# knxhome.net
KiCad netlist of a schematic drawn in EAGLE
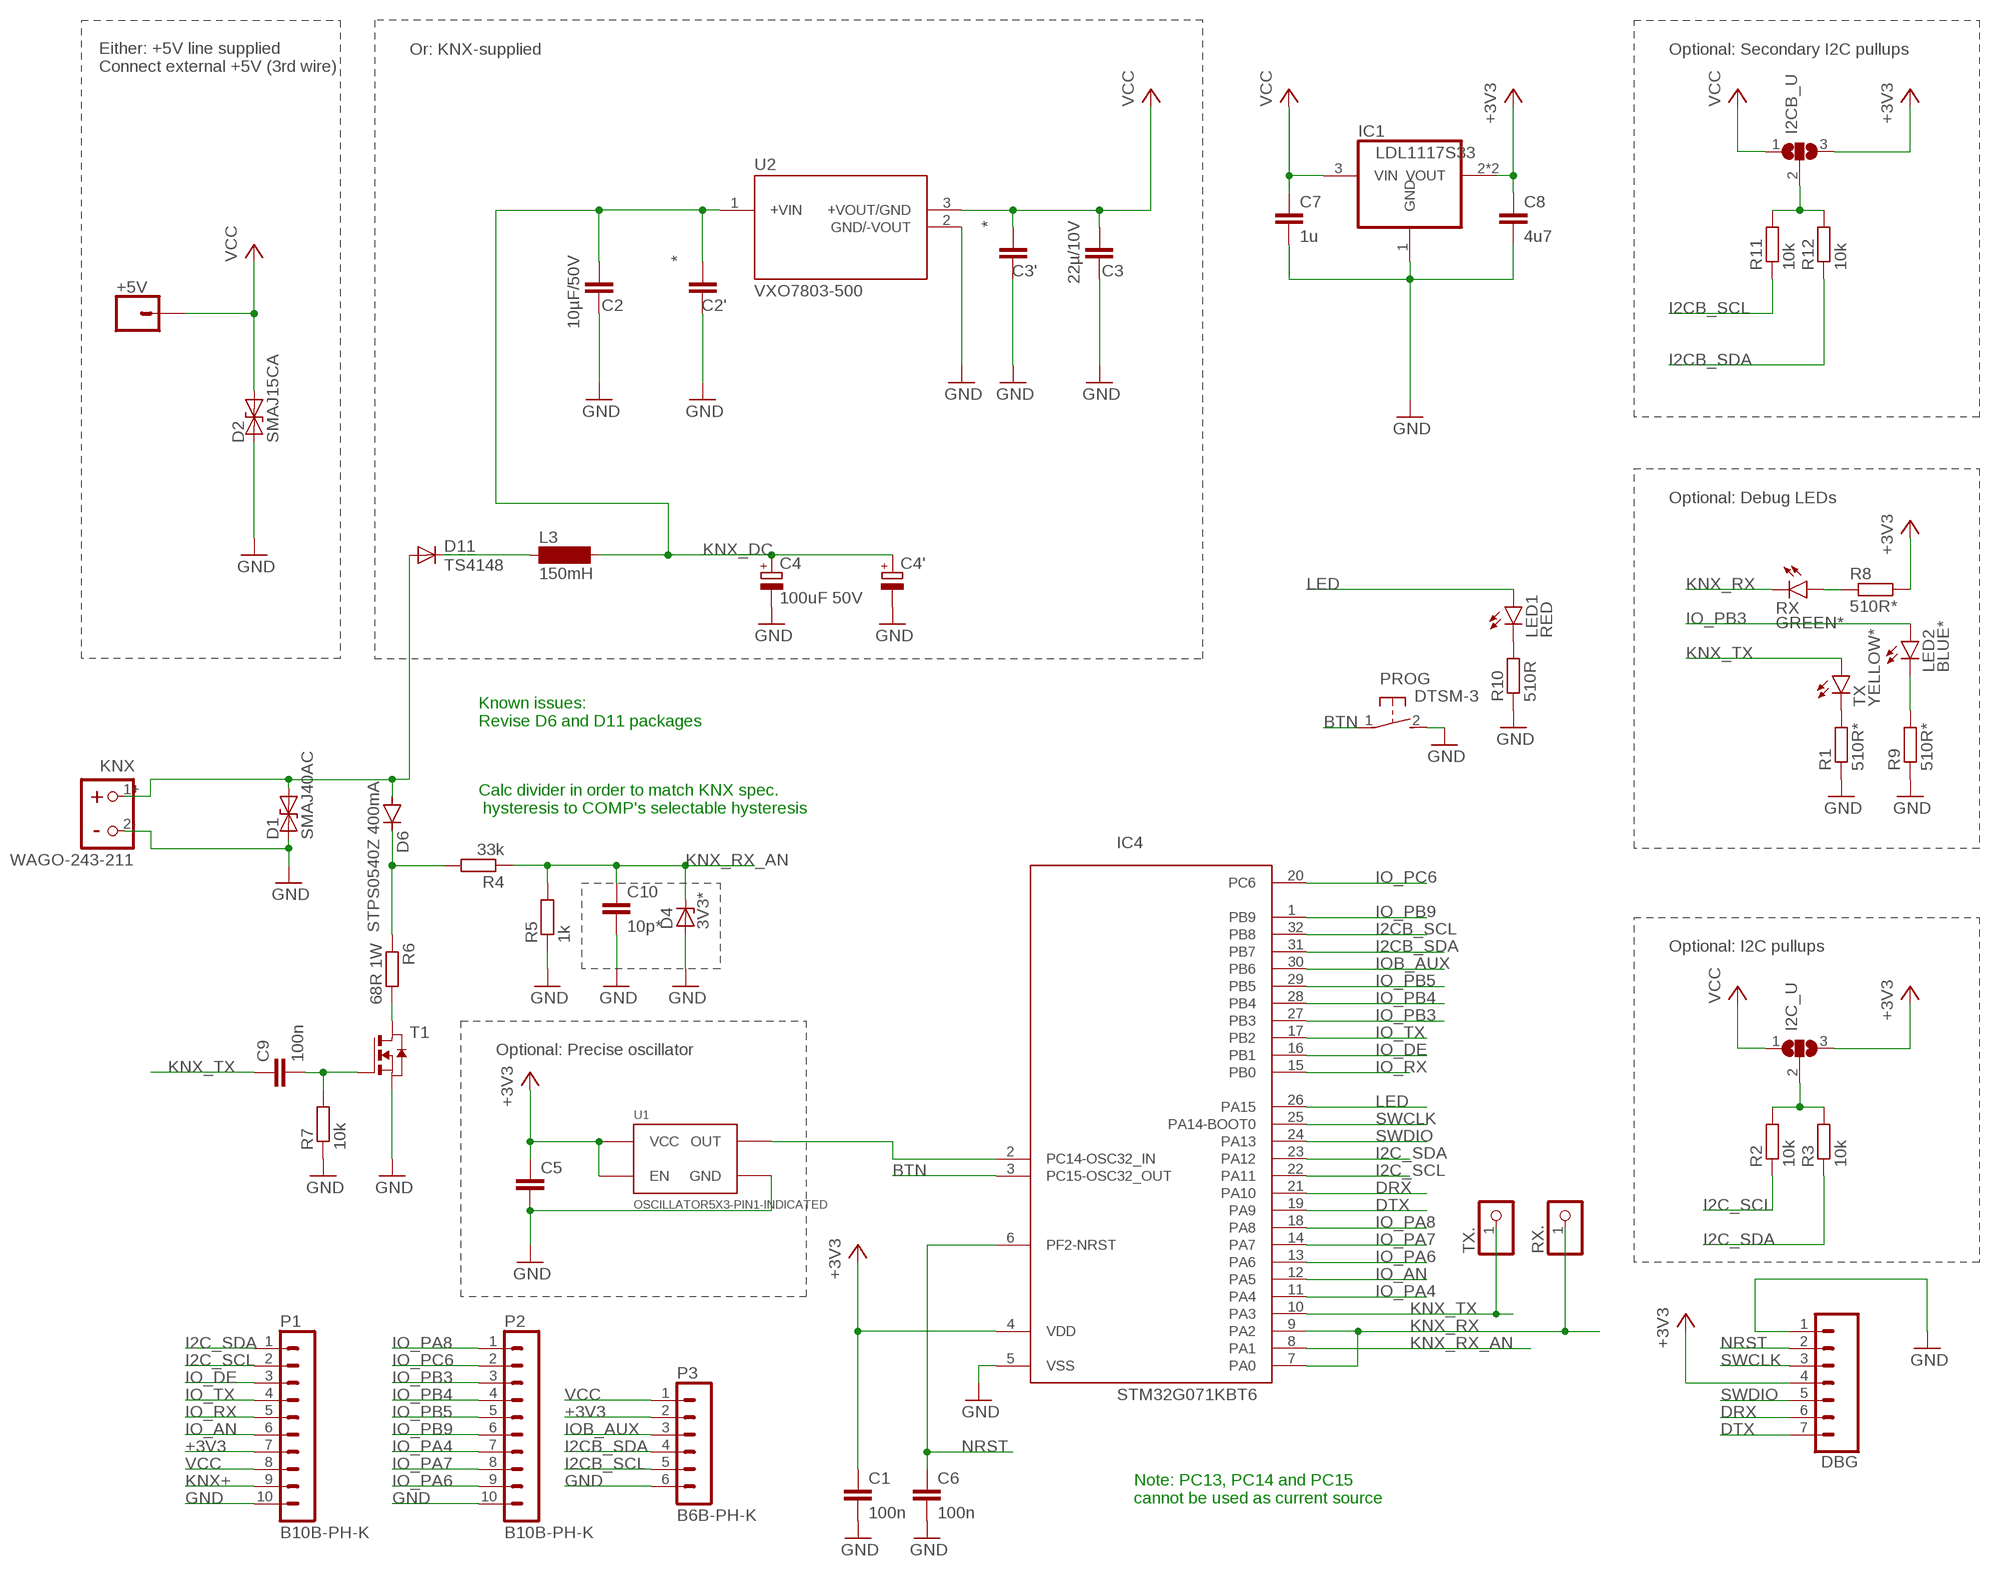
[diagram p0: schematic, sheet 1]

(export (version "E")
  (design (tool "Eeschema 10.0.6"))
  (components
    (comp (ref "+5V")
      (value "CONN_01PTH_LONGPAD")
      (footprint "eagle-import:1X01_LONGPAD")
      (libsource (lib "eagle-import") (part "CONN_01PTH_LONGPAD"))
    )
    (comp (ref "C1")
      (value "100n")
      (footprint "eagle-import:C0805")
      (libsource (lib "eagle-import") (part "C-EUC0805"))
    )
    (comp (ref "C2")
      (value "10µF/50V")
      (footprint "eagle-import:C1210")
      (libsource (lib "eagle-import") (part "C-EUC1210"))
    )
    (comp (ref "C2'")
      (value "*")
      (footprint "eagle-import:C1210")
      (libsource (lib "eagle-import") (part "C-EUC1210"))
    )
    (comp (ref "C3")
      (value "22µ/10V")
      (footprint "eagle-import:C1210")
      (libsource (lib "eagle-import") (part "C-EUC1210"))
    )
    (comp (ref "C3'")
      (value "*")
      (footprint "eagle-import:C1210")
      (libsource (lib "eagle-import") (part "C-EUC1210"))
    )
    (comp (ref "C4")
      (value "100uF 50V")
      (footprint "eagle-import:E3,5-8")
      (libsource (lib "eagle-import") (part "CPOL-EUE3.5-8"))
    )
    (comp (ref "C4'")
      (value "CPOL-EU153CLV-0810")
      (footprint "eagle-import:153CLV-0810")
      (libsource (lib "eagle-import") (part "resistor_348_CPOL-EU153CLV-0810"))
    )
    (comp (ref "C5")
      (value "C-EUC0805")
      (footprint "eagle-import:C0805")
      (libsource (lib "eagle-import") (part "C-EUC0805"))
    )
    (comp (ref "C6")
      (value "100n")
      (footprint "eagle-import:C0805")
      (libsource (lib "eagle-import") (part "C-EUC0805"))
    )
    (comp (ref "C7")
      (value "1u")
      (footprint "eagle-import:C0805")
      (libsource (lib "eagle-import") (part "C-EUC0805"))
    )
    (comp (ref "C8")
      (value "4u7")
      (footprint "eagle-import:C0805")
      (libsource (lib "eagle-import") (part "C-EUC0805"))
    )
    (comp (ref "C9")
      (value "100n")
      (footprint "eagle-import:C0805")
      (libsource (lib "eagle-import") (part "C-EUC0805"))
    )
    (comp (ref "C10")
      (value "10p*")
      (footprint "eagle-import:C0805")
      (libsource (lib "eagle-import") (part "C-EUC0805"))
    )
    (comp (ref "D1")
      (value "SMAJ40AC")
      (footprint "eagle-import:DO-214AC")
      (libsource (lib "eagle-import") (part "SMAJ40AC"))
    )
    (comp (ref "D2")
      (value "SMAJ15CA")
      (footprint "eagle-import:DO-214AC")
      (libsource (lib "eagle-import") (part "SMAJ40AC"))
    )
    (comp (ref "D4")
      (value "3V3*")
      (footprint "eagle-import:SOT23")
      (libsource (lib "eagle-import") (part "ZENER-DIODESOT23"))
    )
    (comp (ref "D6")
      (value "STPS0540Z 400mA")
      (footprint "eagle-import:SOD123")
      (libsource (lib "eagle-import") (part "diode_210_DIODE-SOD123"))
    )
    (comp (ref "D11")
      (value "TS4148")
      (footprint "eagle-import:SOD123")
      (libsource (lib "eagle-import") (part "DIODE-SOD123"))
    )
    (comp (ref "DBG")
      (value "CONN_07LOCK")
      (footprint "eagle-import:1X07_LOCK")
      (libsource (lib "eagle-import") (part "CONN_07LOCK"))
    )
    (comp (ref "I2CB_U")
      (value "SJ2W")
      (footprint "eagle-import:SJ_2")
      (libsource (lib "eagle-import") (part "SJ2W"))
    )
    (comp (ref "I2C_U")
      (value "SJ2W")
      (footprint "eagle-import:SJ_2")
      (libsource (lib "eagle-import") (part "SJ2W"))
    )
    (comp (ref "IC1")
      (value "LDL1117S33")
      (footprint "eagle-import:SOT223")
      (fields (field (name "MPN") "REG1117"))
      (libsource (lib "eagle-import") (part "REG1117"))
    )
    (comp (ref "IC4")
      (value "STM32G071KBT6")
      (footprint "eagle-import:LQFP32")
      (libsource (lib "eagle-import") (part "STM32G071KBT6"))
    )
    (comp (ref "KNX")
      (value "WAGO-243-211")
      (footprint "eagle-import:WAGO-243-211")
      (libsource (lib "eagle-import") (part "WAGO-243-211"))
    )
    (comp (ref "L3")
      (value "150mH")
      (footprint "eagle-import:BS11_LIEGEND")
      (libsource (lib "eagle-import") (part "SD12BS11_LIEGEND"))
    )
    (comp (ref "LED1")
      (value "RED")
      (footprint "eagle-import:CHIPLED_1206")
      (libsource (lib "eagle-import") (part "LEDCHIPLED_1206"))
    )
    (comp (ref "LED2")
      (value "BLUE*")
      (footprint "eagle-import:CHIPLED_1206")
      (libsource (lib "eagle-import") (part "LEDCHIPLED_1206"))
    )
    (comp (ref "P1")
      (value "B10B-PH-K")
      (footprint "eagle-import:B10B-PH-K")
      (libsource (lib "eagle-import") (part "B10B-PH-K"))
    )
    (comp (ref "P2")
      (value "B10B-PH-K")
      (footprint "eagle-import:B10B-PH-K")
      (libsource (lib "eagle-import") (part "B10B-PH-K"))
    )
    (comp (ref "P3")
      (value "B6B-PH-K")
      (footprint "eagle-import:B6B-PH-K")
      (libsource (lib "eagle-import") (part "B6B-PH-K"))
    )
    (comp (ref "PROG")
      (value "DTSM-3")
      (footprint "eagle-import:DTSM-3")
      (libsource (lib "eagle-import") (part "DTSM-3"))
    )
    (comp (ref "R1")
      (value "510R*")
      (footprint "eagle-import:R0805")
      (libsource (lib "eagle-import") (part "R-EU_R0805"))
    )
    (comp (ref "R2")
      (value "10k")
      (footprint "eagle-import:R0805")
      (libsource (lib "eagle-import") (part "R-EU_R0805"))
    )
    (comp (ref "R3")
      (value "10k")
      (footprint "eagle-import:R0805")
      (libsource (lib "eagle-import") (part "R-EU_R0805"))
    )
    (comp (ref "R4")
      (value "33k")
      (footprint "eagle-import:R0805")
      (libsource (lib "eagle-import") (part "R-EU_R0805"))
    )
    (comp (ref "R5")
      (value "1k")
      (footprint "eagle-import:R0805")
      (libsource (lib "eagle-import") (part "R-EU_R0805"))
    )
    (comp (ref "R6")
      (value "68R 1W")
      (footprint "eagle-import:R2512")
      (libsource (lib "eagle-import") (part "R-EU_R2512"))
    )
    (comp (ref "R7")
      (value "10k")
      (footprint "eagle-import:R0805")
      (libsource (lib "eagle-import") (part "R-EU_R0805"))
    )
    (comp (ref "R8")
      (value "510R*")
      (footprint "eagle-import:R0805")
      (libsource (lib "eagle-import") (part "R-EU_R0805"))
    )
    (comp (ref "R9")
      (value "510R*")
      (footprint "eagle-import:R0805")
      (libsource (lib "eagle-import") (part "R-EU_R0805"))
    )
    (comp (ref "R10")
      (value "510R")
      (footprint "eagle-import:R0805")
      (libsource (lib "eagle-import") (part "R-EU_R0805"))
    )
    (comp (ref "R11")
      (value "10k")
      (footprint "eagle-import:R0805")
      (libsource (lib "eagle-import") (part "R-EU_R0805"))
    )
    (comp (ref "R12")
      (value "10k")
      (footprint "eagle-import:R0805")
      (libsource (lib "eagle-import") (part "R-EU_R0805"))
    )
    (comp (ref "RX")
      (value "GREEN*")
      (footprint "eagle-import:CHIPLED_1206")
      (libsource (lib "eagle-import") (part "LEDCHIPLED_1206"))
    )
    (comp (ref "RX.")
      (value "PINHD-1X1")
      (footprint "eagle-import:1X01")
      (libsource (lib "eagle-import") (part "PINHD-1X1"))
    )
    (comp (ref "T1")
      (value "NMOSSOT23")
      (footprint "eagle-import:SOT-23")
      (libsource (lib "eagle-import") (part "NMOSSOT23"))
    )
    (comp (ref "TX")
      (value "YELLOW*")
      (footprint "eagle-import:CHIPLED_1206")
      (libsource (lib "eagle-import") (part "LEDCHIPLED_1206"))
    )
    (comp (ref "TX.")
      (value "PINHD-1X1")
      (footprint "eagle-import:1X01")
      (libsource (lib "eagle-import") (part "PINHD-1X1"))
    )
    (comp (ref "U1")
      (value "OSCILLATOR5X3-PIN1-INDICATED")
      (footprint "eagle-import:CRYSTAL-OSC-SMD-5X3")
      (libsource (lib "eagle-import") (part "OSCILLATOR5X3-PIN1-INDICATED"))
    )
    (comp (ref "U2")
      (value "VXO7803-500")
      (footprint "eagle-import:CONV_VXO7803-500")
      (fields (field (name "MANUFACTURER") "CUI Inc"))
      (libsource (lib "eagle-import") (part "VXO7803-500"))
    )
  )
  (nets
    (net (code "1") (name "+3V3") (class "Default")
      (node (ref "C1") (pin "1") (pinfunction "1_1") (pintype "passive"))
      (node (ref "C5") (pin "1") (pinfunction "1_1") (pintype "passive"))
      (node (ref "C8") (pin "1") (pinfunction "1_1") (pintype "passive"))
      (node (ref "DBG") (pin "4") (pinfunction "4_4") (pintype "passive"))
      (node (ref "I2CB_U") (pin "3") (pinfunction "3_3") (pintype "passive"))
      (node (ref "I2C_U") (pin "3") (pinfunction "3_3") (pintype "passive"))
      (node (ref "IC1") (pin "2") (pinfunction "VOUT_2") (pintype "output"))
      (node (ref "IC1") (pin "4") (pinfunction "VOUT_4") (pintype "output"))
      (node (ref "IC4") (pin "4") (pinfunction "VDD_4") (pintype "power_in"))
      (node (ref "P1") (pin "7") (pinfunction "7_7") (pintype "passive"))
      (node (ref "P3") (pin "2") (pinfunction "2_2") (pintype "passive"))
      (node (ref "R8") (pin "2") (pinfunction "2_2") (pintype "passive"))
      (node (ref "U1") (pin "1") (pinfunction "EN_1") (pintype "bidirectional"))
      (node (ref "U1") (pin "4") (pinfunction "VCC_4") (pintype "bidirectional"))
    )
    (net (code "2") (name "/BTN") (class "Default")
      (node (ref "IC4") (pin "3") (pinfunction "PC15-OSC32_OUT_3") (pintype "bidirectional"))
      (node (ref "PROG") (pin "1") (pinfunction "1_1") (pintype "passive"))
    )
    (net (code "3") (name "/DRX") (class "Default")
      (node (ref "DBG") (pin "6") (pinfunction "6_6") (pintype "passive"))
      (node (ref "IC4") (pin "21") (pinfunction "PA10_21") (pintype "bidirectional"))
    )
    (net (code "4") (name "/DTX") (class "Default")
      (node (ref "DBG") (pin "7") (pinfunction "7_7") (pintype "passive"))
      (node (ref "IC4") (pin "19") (pinfunction "PA9_19") (pintype "bidirectional"))
    )
    (net (code "5") (name "/I2CB_SCL") (class "Default")
      (node (ref "IC4") (pin "32") (pinfunction "PB8_32") (pintype "bidirectional"))
      (node (ref "P3") (pin "5") (pinfunction "5_5") (pintype "passive"))
      (node (ref "R11") (pin "1") (pinfunction "1_1") (pintype "passive"))
    )
    (net (code "6") (name "/I2CB_SDA") (class "Default")
      (node (ref "IC4") (pin "31") (pinfunction "PB7_31") (pintype "bidirectional"))
      (node (ref "P3") (pin "4") (pinfunction "4_4") (pintype "passive"))
      (node (ref "R12") (pin "1") (pinfunction "1_1") (pintype "passive"))
    )
    (net (code "7") (name "/I2C_SCL") (class "Default")
      (node (ref "IC4") (pin "22") (pinfunction "PA11_22") (pintype "bidirectional"))
      (node (ref "P1") (pin "2") (pinfunction "2_2") (pintype "passive"))
      (node (ref "R2") (pin "1") (pinfunction "1_1") (pintype "passive"))
    )
    (net (code "8") (name "/I2C_SDA") (class "Default")
      (node (ref "IC4") (pin "23") (pinfunction "PA12_23") (pintype "bidirectional"))
      (node (ref "P1") (pin "1") (pinfunction "1_1") (pintype "passive"))
      (node (ref "R3") (pin "1") (pinfunction "1_1") (pintype "passive"))
    )
    (net (code "9") (name "/IOB_AUX") (class "Default")
      (node (ref "IC4") (pin "30") (pinfunction "PB6_30") (pintype "bidirectional"))
      (node (ref "P3") (pin "3") (pinfunction "3_3") (pintype "passive"))
    )
    (net (code "10") (name "/IO_AN") (class "Default")
      (node (ref "IC4") (pin "12") (pinfunction "PA5_12") (pintype "bidirectional"))
      (node (ref "P1") (pin "6") (pinfunction "6_6") (pintype "passive"))
    )
    (net (code "11") (name "/IO_DE") (class "Default")
      (node (ref "IC4") (pin "16") (pinfunction "PB1_16") (pintype "bidirectional"))
      (node (ref "P1") (pin "3") (pinfunction "3_3") (pintype "passive"))
    )
    (net (code "12") (name "/IO_PA4") (class "Default")
      (node (ref "IC4") (pin "11") (pinfunction "PA4_11") (pintype "bidirectional"))
      (node (ref "P2") (pin "7") (pinfunction "7_7") (pintype "passive"))
    )
    (net (code "13") (name "/IO_PA6") (class "Default")
      (node (ref "IC4") (pin "13") (pinfunction "PA6_13") (pintype "bidirectional"))
      (node (ref "P2") (pin "9") (pinfunction "9_9") (pintype "passive"))
    )
    (net (code "14") (name "/IO_PA7") (class "Default")
      (node (ref "IC4") (pin "14") (pinfunction "PA7_14") (pintype "bidirectional"))
      (node (ref "P2") (pin "8") (pinfunction "8_8") (pintype "passive"))
    )
    (net (code "15") (name "/IO_PA8") (class "Default")
      (node (ref "IC4") (pin "18") (pinfunction "PA8_18") (pintype "bidirectional"))
      (node (ref "P2") (pin "1") (pinfunction "1_1") (pintype "passive"))
    )
    (net (code "16") (name "/IO_PB3") (class "Default")
      (node (ref "IC4") (pin "27") (pinfunction "PB3_27") (pintype "bidirectional"))
      (node (ref "LED2") (pin "A") (pinfunction "A_A") (pintype "passive"))
      (node (ref "P2") (pin "3") (pinfunction "3_3") (pintype "passive"))
    )
    (net (code "17") (name "/IO_PB4") (class "Default")
      (node (ref "IC4") (pin "28") (pinfunction "PB4_28") (pintype "bidirectional"))
      (node (ref "P2") (pin "4") (pinfunction "4_4") (pintype "passive"))
    )
    (net (code "18") (name "/IO_PB5") (class "Default")
      (node (ref "IC4") (pin "29") (pinfunction "PB5_29") (pintype "bidirectional"))
      (node (ref "P2") (pin "5") (pinfunction "5_5") (pintype "passive"))
    )
    (net (code "19") (name "/IO_PB9") (class "Default")
      (node (ref "IC4") (pin "1") (pinfunction "PB9_1") (pintype "bidirectional"))
      (node (ref "P2") (pin "6") (pinfunction "6_6") (pintype "passive"))
    )
    (net (code "20") (name "/IO_PC6") (class "Default")
      (node (ref "IC4") (pin "20") (pinfunction "PC6_20") (pintype "bidirectional"))
      (node (ref "P2") (pin "2") (pinfunction "2_2") (pintype "passive"))
    )
    (net (code "21") (name "/IO_RX") (class "Default")
      (node (ref "IC4") (pin "15") (pinfunction "PB0_15") (pintype "bidirectional"))
      (node (ref "P1") (pin "5") (pinfunction "5_5") (pintype "passive"))
    )
    (net (code "22") (name "/IO_TX") (class "Default")
      (node (ref "IC4") (pin "17") (pinfunction "PB2_17") (pintype "bidirectional"))
      (node (ref "P1") (pin "4") (pinfunction "4_4") (pintype "passive"))
    )
    (net (code "23") (name "/KNX+") (class "Default")
      (node (ref "D1") (pin "C") (pinfunction "C_C") (pintype "passive"))
      (node (ref "D11") (pin "A") (pinfunction "A_A") (pintype "passive"))
      (node (ref "D6") (pin "A") (pinfunction "A_A") (pintype "passive"))
      (node (ref "KNX") (pin "1+") (pinfunction "1+_1+") (pintype "passive"))
      (node (ref "P1") (pin "9") (pinfunction "9_9") (pintype "passive"))
    )
    (net (code "24") (name "/KNX_DC") (class "Default")
      (node (ref "C2") (pin "2") (pinfunction "2_2") (pintype "passive"))
      (node (ref "C2'") (pin "2") (pinfunction "2_2") (pintype "passive"))
      (node (ref "C4") (pin "+") (pinfunction "+_+") (pintype "passive"))
      (node (ref "C4'") (pin "+") (pinfunction "+_+") (pintype "passive"))
      (node (ref "L3") (pin "2") (pinfunction "2_2") (pintype "passive"))
      (node (ref "U2") (pin "1") (pinfunction "+VIN_1") (pintype "input"))
    )
    (net (code "25") (name "/KNX_RX") (class "Default")
      (node (ref "IC4") (pin "7") (pinfunction "PA0_7") (pintype "bidirectional"))
      (node (ref "IC4") (pin "9") (pinfunction "PA2_9") (pintype "bidirectional"))
      (node (ref "RX") (pin "C") (pinfunction "C_C") (pintype "passive"))
      (node (ref "RX.") (pin "1") (pinfunction "1_1") (pintype "passive"))
    )
    (net (code "26") (name "/KNX_RX_AN") (class "Default")
      (node (ref "C10") (pin "1") (pinfunction "1_1") (pintype "passive"))
      (node (ref "D4") (pin "3") (pinfunction "C_3") (pintype "passive"))
      (node (ref "IC4") (pin "8") (pinfunction "PA1_8") (pintype "bidirectional"))
      (node (ref "R4") (pin "1") (pinfunction "1_1") (pintype "passive"))
      (node (ref "R5") (pin "2") (pinfunction "2_2") (pintype "passive"))
    )
    (net (code "27") (name "/KNX_TX") (class "Default")
      (node (ref "C9") (pin "1") (pinfunction "1_1") (pintype "passive"))
      (node (ref "IC4") (pin "10") (pinfunction "PA3_10") (pintype "bidirectional"))
      (node (ref "TX") (pin "A") (pinfunction "A_A") (pintype "passive"))
      (node (ref "TX.") (pin "1") (pinfunction "1_1") (pintype "passive"))
    )
    (net (code "28") (name "/LED") (class "Default")
      (node (ref "IC4") (pin "26") (pinfunction "PA15_26") (pintype "bidirectional"))
      (node (ref "LED1") (pin "A") (pinfunction "A_A") (pintype "passive"))
    )
    (net (code "29") (name "/NRST") (class "Default")
      (node (ref "C6") (pin "1") (pinfunction "1_1") (pintype "passive"))
      (node (ref "DBG") (pin "2") (pinfunction "2_2") (pintype "passive"))
      (node (ref "IC4") (pin "6") (pinfunction "PF2-NRST_6") (pintype "bidirectional"))
    )
    (net (code "30") (name "/SWCLK") (class "Default")
      (node (ref "DBG") (pin "3") (pinfunction "3_3") (pintype "passive"))
      (node (ref "IC4") (pin "25") (pinfunction "PA14-BOOT0_25") (pintype "bidirectional"))
    )
    (net (code "31") (name "/SWDIO") (class "Default")
      (node (ref "DBG") (pin "5") (pinfunction "5_5") (pintype "passive"))
      (node (ref "IC4") (pin "24") (pinfunction "PA13_24") (pintype "bidirectional"))
    )
    (net (code "32") (name "GND") (class "Default")
      (node (ref "C1") (pin "2") (pinfunction "2_2") (pintype "passive"))
      (node (ref "C10") (pin "2") (pinfunction "2_2") (pintype "passive"))
      (node (ref "C2") (pin "1") (pinfunction "1_1") (pintype "passive"))
      (node (ref "C2'") (pin "1") (pinfunction "1_1") (pintype "passive"))
      (node (ref "C3") (pin "1") (pinfunction "1_1") (pintype "passive"))
      (node (ref "C3'") (pin "1") (pinfunction "1_1") (pintype "passive"))
      (node (ref "C4") (pin "-") (pinfunction "-_-") (pintype "passive"))
      (node (ref "C4'") (pin "-") (pinfunction "-_-") (pintype "passive"))
      (node (ref "C5") (pin "2") (pinfunction "2_2") (pintype "passive"))
      (node (ref "C6") (pin "2") (pinfunction "2_2") (pintype "passive"))
      (node (ref "C7") (pin "2") (pinfunction "2_2") (pintype "passive"))
      (node (ref "C8") (pin "2") (pinfunction "2_2") (pintype "passive"))
      (node (ref "D1") (pin "A") (pinfunction "A_A") (pintype "passive"))
      (node (ref "D2") (pin "A") (pinfunction "A_A") (pintype "passive"))
      (node (ref "D4") (pin "1") (pinfunction "A_1") (pintype "passive"))
      (node (ref "DBG") (pin "1") (pinfunction "1_1") (pintype "passive"))
      (node (ref "IC1") (pin "1") (pinfunction "GND_1") (pintype "power_in"))
      (node (ref "IC4") (pin "5") (pinfunction "VSS_5") (pintype "power_in"))
      (node (ref "KNX") (pin "2-") (pinfunction "2-_2-") (pintype "passive"))
      (node (ref "P1") (pin "10") (pinfunction "10_10") (pintype "passive"))
      (node (ref "P2") (pin "10") (pinfunction "10_10") (pintype "passive"))
      (node (ref "P3") (pin "6") (pinfunction "6_6") (pintype "passive"))
      (node (ref "PROG") (pin "2") (pinfunction "2_2") (pintype "passive"))
      (node (ref "R1") (pin "1") (pinfunction "1_1") (pintype "passive"))
      (node (ref "R10") (pin "1") (pinfunction "1_1") (pintype "passive"))
      (node (ref "R5") (pin "1") (pinfunction "1_1") (pintype "passive"))
      (node (ref "R7") (pin "1") (pinfunction "1_1") (pintype "passive"))
      (node (ref "R9") (pin "1") (pinfunction "1_1") (pintype "passive"))
      (node (ref "T1") (pin "2") (pinfunction "S_2") (pintype "passive"))
      (node (ref "U1") (pin "2") (pinfunction "GND_2") (pintype "bidirectional"))
      (node (ref "U2") (pin "2") (pinfunction "GND/-VOUT_2") (pintype "output"))
    )
    (net (code "33") (name "Net-(D6-PadC)") (class "Default")
      (node (ref "D6") (pin "C") (pinfunction "C_C") (pintype "passive"))
      (node (ref "R4") (pin "2") (pinfunction "2_2") (pintype "passive"))
      (node (ref "R6") (pin "1") (pinfunction "1_1") (pintype "passive"))
    )
    (net (code "34") (name "Net-(D11-PadC)") (class "Default")
      (node (ref "D11") (pin "C") (pinfunction "C_C") (pintype "passive"))
      (node (ref "L3") (pin "1") (pinfunction "1_1") (pintype "passive"))
    )
    (net (code "35") (name "Net-(I2CB_U-Pad2)") (class "Default")
      (node (ref "I2CB_U") (pin "2") (pinfunction "2_2") (pintype "passive"))
      (node (ref "R11") (pin "2") (pinfunction "2_2") (pintype "passive"))
      (node (ref "R12") (pin "2") (pinfunction "2_2") (pintype "passive"))
    )
    (net (code "36") (name "Net-(I2C_U-Pad2)") (class "Default")
      (node (ref "I2C_U") (pin "2") (pinfunction "2_2") (pintype "passive"))
      (node (ref "R2") (pin "2") (pinfunction "2_2") (pintype "passive"))
      (node (ref "R3") (pin "2") (pinfunction "2_2") (pintype "passive"))
    )
    (net (code "37") (name "Net-(IC4-PC14-OSC32_IN)") (class "Default")
      (node (ref "IC4") (pin "2") (pinfunction "PC14-OSC32_IN_2") (pintype "bidirectional"))
      (node (ref "U1") (pin "3") (pinfunction "OUT_3") (pintype "bidirectional"))
    )
    (net (code "38") (name "Net-(LED1-PadC)") (class "Default")
      (node (ref "LED1") (pin "C") (pinfunction "C_C") (pintype "passive"))
      (node (ref "R10") (pin "2") (pinfunction "2_2") (pintype "passive"))
    )
    (net (code "39") (name "Net-(LED2-PadC)") (class "Default")
      (node (ref "LED2") (pin "C") (pinfunction "C_C") (pintype "passive"))
      (node (ref "R9") (pin "2") (pinfunction "2_2") (pintype "passive"))
    )
    (net (code "40") (name "Net-(R1-Pad2)") (class "Default")
      (node (ref "R1") (pin "2") (pinfunction "2_2") (pintype "passive"))
      (node (ref "TX") (pin "C") (pinfunction "C_C") (pintype "passive"))
    )
    (net (code "41") (name "Net-(R8-Pad1)") (class "Default")
      (node (ref "R8") (pin "1") (pinfunction "1_1") (pintype "passive"))
      (node (ref "RX") (pin "A") (pinfunction "A_A") (pintype "passive"))
    )
    (net (code "42") (name "Net-(T1-D)") (class "Default")
      (node (ref "R6") (pin "2") (pinfunction "2_2") (pintype "passive"))
      (node (ref "T1") (pin "1") (pinfunction "D_1") (pintype "passive"))
    )
    (net (code "43") (name "Net-(T1-G)") (class "Default")
      (node (ref "C9") (pin "2") (pinfunction "2_2") (pintype "passive"))
      (node (ref "R7") (pin "2") (pinfunction "2_2") (pintype "passive"))
      (node (ref "T1") (pin "3") (pinfunction "G_3") (pintype "passive"))
    )
    (net (code "44") (name "VCC") (class "Default")
      (node (ref "+5V") (pin "1") (pinfunction "1_1") (pintype "passive"))
      (node (ref "C3") (pin "2") (pinfunction "2_2") (pintype "passive"))
      (node (ref "C3'") (pin "2") (pinfunction "2_2") (pintype "passive"))
      (node (ref "C7") (pin "1") (pinfunction "1_1") (pintype "passive"))
      (node (ref "D2") (pin "C") (pinfunction "C_C") (pintype "passive"))
      (node (ref "I2CB_U") (pin "1") (pinfunction "1_1") (pintype "passive"))
      (node (ref "I2C_U") (pin "1") (pinfunction "1_1") (pintype "passive"))
      (node (ref "IC1") (pin "3") (pinfunction "VIN_3") (pintype "input"))
      (node (ref "P1") (pin "8") (pinfunction "8_8") (pintype "passive"))
      (node (ref "P3") (pin "1") (pinfunction "1_1") (pintype "passive"))
      (node (ref "U2") (pin "3") (pinfunction "+VOUT/GND_3") (pintype "output"))
    )
  )
)
